# panel.net
KiCad netlist of a schematic drawn in EAGLE
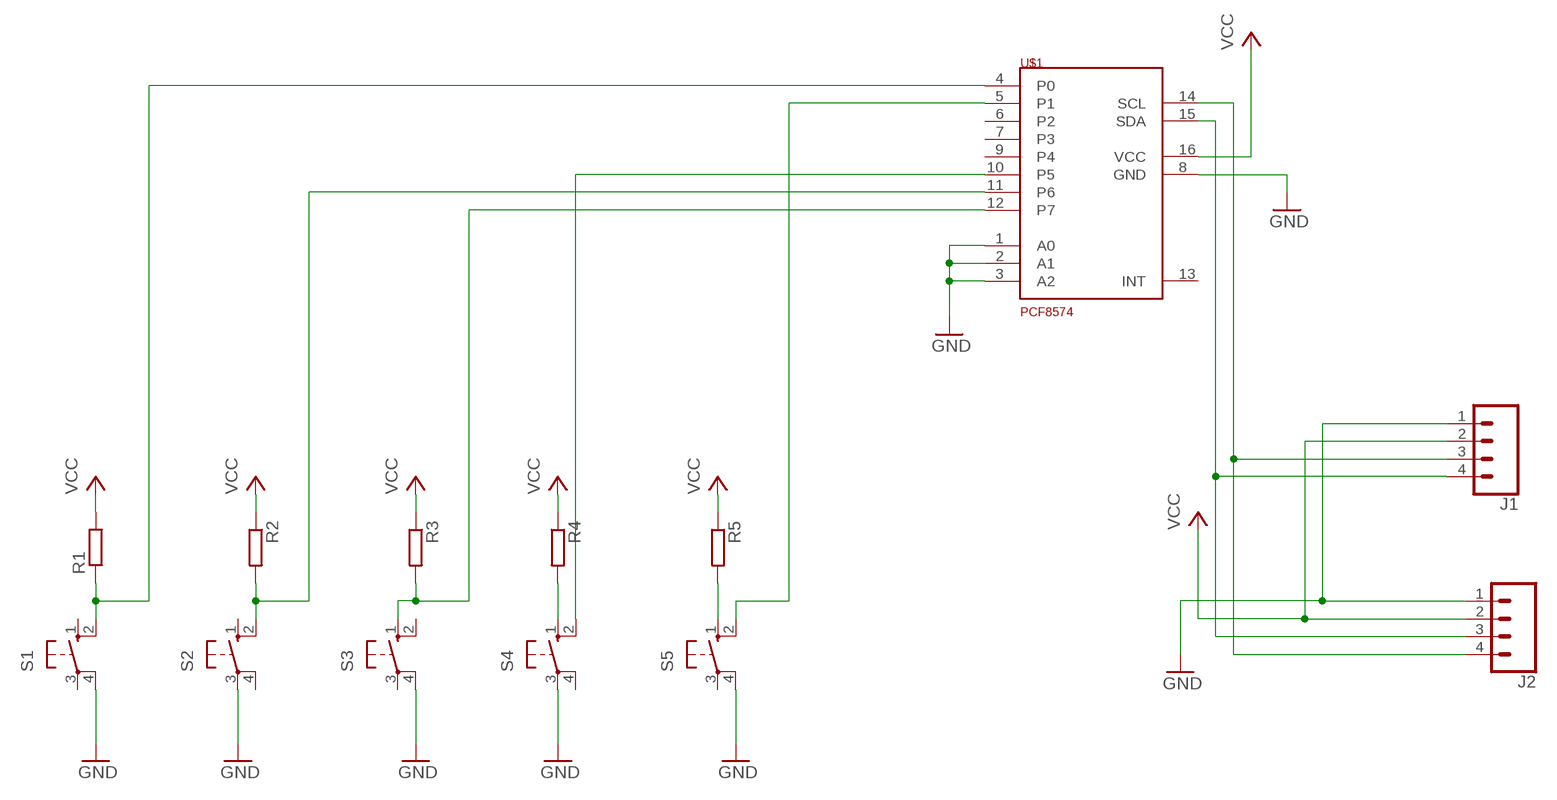
[diagram p0: schematic, sheet 1]

(export (version "E")
  (design (tool "Eeschema 10.0.6"))
  (components
    (comp (ref "J1")
      (value "CONN_04PTH")
      (footprint "eagle-import:1X04")
      (libsource (lib "eagle-import") (part "CONN_04PTH"))
    )
    (comp (ref "J2")
      (value "CONN_04PTH")
      (footprint "eagle-import:1X04")
      (libsource (lib "eagle-import") (part "CONN_04PTH"))
    )
    (comp (ref "R1")
      (value "R-EU_0204/7")
      (footprint "eagle-import:0204_7")
      (libsource (lib "eagle-import") (part "R-EU_0204/7"))
    )
    (comp (ref "R2")
      (value "R-EU_0204/7")
      (footprint "eagle-import:0204_7")
      (libsource (lib "eagle-import") (part "R-EU_0204/7"))
    )
    (comp (ref "R3")
      (value "R-EU_0204/7")
      (footprint "eagle-import:0204_7")
      (libsource (lib "eagle-import") (part "R-EU_0204/7"))
    )
    (comp (ref "R4")
      (value "R-EU_0204/7")
      (footprint "eagle-import:0204_7")
      (libsource (lib "eagle-import") (part "R-EU_0204/7"))
    )
    (comp (ref "R5")
      (value "R-EU_0204/7")
      (footprint "eagle-import:0204_7")
      (libsource (lib "eagle-import") (part "R-EU_0204/7"))
    )
    (comp (ref "S1")
      (value "10-XX")
      (footprint "eagle-import:B3F-10XX")
      (fields (field (name "MPN") "B3F-1000"))
      (libsource (lib "eagle-import") (part "10-XX"))
    )
    (comp (ref "S2")
      (value "10-XX")
      (footprint "eagle-import:B3F-10XX")
      (fields (field (name "MPN") "B3F-1000"))
      (libsource (lib "eagle-import") (part "10-XX"))
    )
    (comp (ref "S3")
      (value "10-XX")
      (footprint "eagle-import:B3F-10XX")
      (fields (field (name "MPN") "B3F-1000"))
      (libsource (lib "eagle-import") (part "10-XX"))
    )
    (comp (ref "S4")
      (value "10-XX")
      (footprint "eagle-import:B3F-10XX")
      (fields (field (name "MPN") "B3F-1000"))
      (libsource (lib "eagle-import") (part "10-XX"))
    )
    (comp (ref "S5")
      (value "10-XX")
      (footprint "eagle-import:B3F-10XX")
      (fields (field (name "MPN") "B3F-1000"))
      (libsource (lib "eagle-import") (part "10-XX"))
    )
    (comp (ref "U$1")
      (value "PCF8574")
      (footprint "eagle-import:SO16(SW)")
      (libsource (lib "eagle-import") (part "PCF8574"))
    )
  )
  (nets
    (net (code "1") (name "GND") (class "Default")
      (node (ref "J1") (pin "1") (pinfunction "1_1") (pintype "passive"))
      (node (ref "J2") (pin "1") (pinfunction "1_1") (pintype "passive"))
      (node (ref "S1") (pin "4") (pinfunction "P1_4") (pintype "passive"))
      (node (ref "S2") (pin "3") (pinfunction "P_3") (pintype "passive"))
      (node (ref "S3") (pin "4") (pinfunction "P1_4") (pintype "passive"))
      (node (ref "S4") (pin "3") (pinfunction "P_3") (pintype "passive"))
      (node (ref "S5") (pin "4") (pinfunction "P1_4") (pintype "passive"))
      (node (ref "U$1") (pin "1") (pinfunction "A0_1") (pintype "bidirectional"))
      (node (ref "U$1") (pin "2") (pinfunction "A1_2") (pintype "bidirectional"))
      (node (ref "U$1") (pin "3") (pinfunction "A2_3") (pintype "bidirectional"))
      (node (ref "U$1") (pin "8") (pinfunction "GND_8") (pintype "bidirectional"))
    )
    (net (code "2") (name "Net-(S1-S1)") (class "Default")
      (node (ref "R1") (pin "1") (pinfunction "1_1") (pintype "passive"))
      (node (ref "S1") (pin "2") (pinfunction "S1_2") (pintype "passive"))
      (node (ref "U$1") (pin "4") (pinfunction "P0_4") (pintype "bidirectional"))
    )
    (net (code "3") (name "Net-(S2-S1)") (class "Default")
      (node (ref "R2") (pin "2") (pinfunction "2_2") (pintype "passive"))
      (node (ref "S2") (pin "2") (pinfunction "S1_2") (pintype "passive"))
      (node (ref "U$1") (pin "11") (pinfunction "P6_11") (pintype "bidirectional"))
    )
    (net (code "4") (name "Net-(S3-S)") (class "Default")
      (node (ref "R3") (pin "2") (pinfunction "2_2") (pintype "passive"))
      (node (ref "S3") (pin "1") (pinfunction "S_1") (pintype "passive"))
      (node (ref "U$1") (pin "12") (pinfunction "P7_12") (pintype "bidirectional"))
    )
    (net (code "5") (name "Net-(S4-S)") (class "Default")
      (node (ref "R4") (pin "2") (pinfunction "2_2") (pintype "passive"))
      (node (ref "S4") (pin "1") (pinfunction "S_1") (pintype "passive"))
    )
    (net (code "6") (name "Net-(S4-S1)") (class "Default")
      (node (ref "S4") (pin "2") (pinfunction "S1_2") (pintype "passive"))
      (node (ref "U$1") (pin "10") (pinfunction "P5_10") (pintype "bidirectional"))
    )
    (net (code "7") (name "Net-(S5-S)") (class "Default")
      (node (ref "R5") (pin "2") (pinfunction "2_2") (pintype "passive"))
      (node (ref "S5") (pin "1") (pinfunction "S_1") (pintype "passive"))
    )
    (net (code "8") (name "Net-(S5-S1)") (class "Default")
      (node (ref "S5") (pin "2") (pinfunction "S1_2") (pintype "passive"))
      (node (ref "U$1") (pin "5") (pinfunction "P1_5") (pintype "bidirectional"))
    )
    (net (code "9") (name "Net-(U$1-SCL)") (class "Default")
      (node (ref "J1") (pin "3") (pinfunction "3_3") (pintype "passive"))
      (node (ref "J2") (pin "4") (pinfunction "4_4") (pintype "passive"))
      (node (ref "U$1") (pin "14") (pinfunction "SCL_14") (pintype "bidirectional"))
    )
    (net (code "10") (name "Net-(U$1-SDA)") (class "Default")
      (node (ref "J1") (pin "4") (pinfunction "4_4") (pintype "passive"))
      (node (ref "J2") (pin "3") (pinfunction "3_3") (pintype "passive"))
      (node (ref "U$1") (pin "15") (pinfunction "SDA_15") (pintype "bidirectional"))
    )
    (net (code "11") (name "VCC") (class "Default")
      (node (ref "J1") (pin "2") (pinfunction "2_2") (pintype "passive"))
      (node (ref "J2") (pin "2") (pinfunction "2_2") (pintype "passive"))
      (node (ref "R1") (pin "2") (pinfunction "2_2") (pintype "passive"))
      (node (ref "R2") (pin "1") (pinfunction "1_1") (pintype "passive"))
      (node (ref "R3") (pin "1") (pinfunction "1_1") (pintype "passive"))
      (node (ref "R4") (pin "1") (pinfunction "1_1") (pintype "passive"))
      (node (ref "R5") (pin "1") (pinfunction "1_1") (pintype "passive"))
      (node (ref "U$1") (pin "16") (pinfunction "VCC_16") (pintype "bidirectional"))
    )
    (net (code "12") (name "unconnected-(S1-P-Pad3)") (class "Default")
      (node (ref "S1") (pin "3") (pinfunction "P_3") (pintype "passive"))
    )
    (net (code "13") (name "unconnected-(S1-S-Pad1)") (class "Default")
      (node (ref "S1") (pin "1") (pinfunction "S_1") (pintype "passive"))
    )
    (net (code "14") (name "unconnected-(S2-P1-Pad4)") (class "Default")
      (node (ref "S2") (pin "4") (pinfunction "P1_4") (pintype "passive"))
    )
    (net (code "15") (name "unconnected-(S2-S-Pad1)") (class "Default")
      (node (ref "S2") (pin "1") (pinfunction "S_1") (pintype "passive"))
    )
    (net (code "16") (name "unconnected-(S3-P-Pad3)") (class "Default")
      (node (ref "S3") (pin "3") (pinfunction "P_3") (pintype "passive"))
    )
    (net (code "17") (name "unconnected-(S3-S1-Pad2)") (class "Default")
      (node (ref "S3") (pin "2") (pinfunction "S1_2") (pintype "passive"))
    )
    (net (code "18") (name "unconnected-(S4-P1-Pad4)") (class "Default")
      (node (ref "S4") (pin "4") (pinfunction "P1_4") (pintype "passive"))
    )
    (net (code "19") (name "unconnected-(S5-P-Pad3)") (class "Default")
      (node (ref "S5") (pin "3") (pinfunction "P_3") (pintype "passive"))
    )
    (net (code "20") (name "unconnected-(U$1-INT-Pad13)") (class "Default")
      (node (ref "U$1") (pin "13") (pinfunction "INT_13") (pintype "bidirectional"))
    )
    (net (code "21") (name "unconnected-(U$1-P2-Pad6)") (class "Default")
      (node (ref "U$1") (pin "6") (pinfunction "P2_6") (pintype "bidirectional"))
    )
    (net (code "22") (name "unconnected-(U$1-P3-Pad7)") (class "Default")
      (node (ref "U$1") (pin "7") (pinfunction "P3_7") (pintype "bidirectional"))
    )
    (net (code "23") (name "unconnected-(U$1-P4-Pad9)") (class "Default")
      (node (ref "U$1") (pin "9") (pinfunction "P4_9") (pintype "bidirectional"))
    )
  )
)
